# DigiMult_01.net
KiCad netlist of a schematic drawn in EAGLE
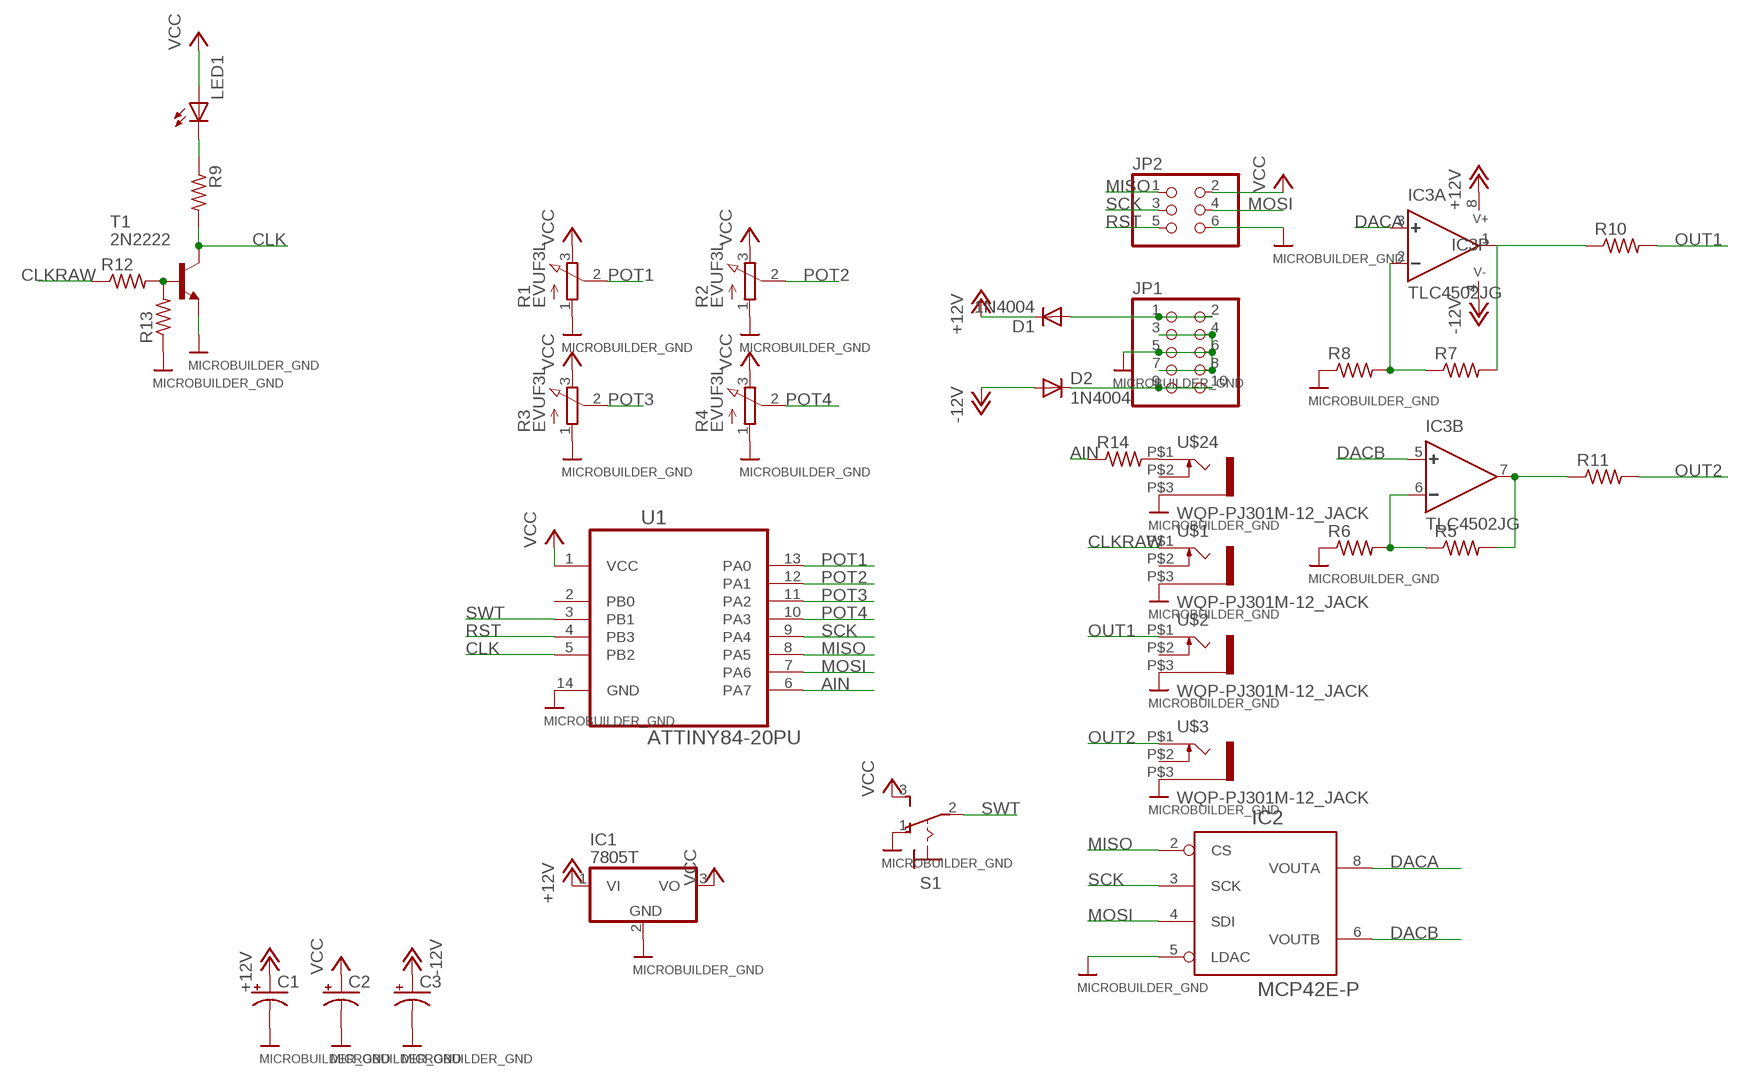
[diagram p0: schematic, sheet 1]

(export (version "E")
  (design (tool "Eeschema 10.0.6"))
  (components
    (comp (ref "C1")
      (value "CPOL-USE2.5-5")
      (footprint "eagle-import:E2,5-5")
      (libsource (lib "eagle-import") (part "CPOL-USE2.5-5"))
    )
    (comp (ref "C2")
      (value "CPOL-USE2.5-5")
      (footprint "eagle-import:E2,5-5")
      (libsource (lib "eagle-import") (part "CPOL-USE2.5-5"))
    )
    (comp (ref "C3")
      (value "CPOL-USE2.5-5")
      (footprint "eagle-import:E2,5-5")
      (libsource (lib "eagle-import") (part "CPOL-USE2.5-5"))
    )
    (comp (ref "D1")
      (value "1N4004")
      (footprint "eagle-import:DO41-10")
      (libsource (lib "eagle-import") (part "1N4004"))
    )
    (comp (ref "D2")
      (value "1N4004")
      (footprint "eagle-import:DO41-10")
      (libsource (lib "eagle-import") (part "1N4004"))
    )
    (comp (ref "IC1")
      (value "7805T")
      (footprint "eagle-import:TO220H")
      (libsource (lib "eagle-import") (part "78T05"))
    )
    (comp (ref "IC2")
      (value "MCP42E-P")
      (footprint "eagle-import:DIL08")
      (libsource (lib "eagle-import") (part "MCP42E-P"))
    )
    (comp (ref "IC3")
      (value "TLC4502JG")
      (footprint "eagle-import:DIL08")
      (libsource (lib "eagle-import") (part "TLC4502JG"))
    )
    (comp (ref "JP1")
      (value "PINHD-2X5/OCT")
      (footprint "eagle-import:2X05")
      (libsource (lib "eagle-import") (part "PINHD-2X5/OCT"))
    )
    (comp (ref "JP2")
      (value "PINHD-2X3/OCT")
      (footprint "eagle-import:2X03")
      (libsource (lib "eagle-import") (part "PINHD-2X3/OCT"))
    )
    (comp (ref "LED1")
      (value "LED3MM")
      (footprint "eagle-import:LED3MM")
      (libsource (lib "eagle-import") (part "LED3MM"))
    )
    (comp (ref "R1")
      (value "EVUF3L")
      (footprint "eagle-import:EVUFXL")
      (libsource (lib "eagle-import") (part "EVULF3"))
    )
    (comp (ref "R2")
      (value "EVUF3L")
      (footprint "eagle-import:EVUFXL")
      (libsource (lib "eagle-import") (part "EVULF3"))
    )
    (comp (ref "R3")
      (value "EVUF3L")
      (footprint "eagle-import:EVUFXL")
      (libsource (lib "eagle-import") (part "EVULF3"))
    )
    (comp (ref "R4")
      (value "EVUF3L")
      (footprint "eagle-import:EVUFXL")
      (libsource (lib "eagle-import") (part "EVULF3"))
    )
    (comp (ref "R5")
      (value "R-US_0204/2V")
      (footprint "eagle-import:0204V")
      (libsource (lib "eagle-import") (part "R-US_0204/2V"))
    )
    (comp (ref "R6")
      (value "R-US_0204/2V")
      (footprint "eagle-import:0204V")
      (libsource (lib "eagle-import") (part "R-US_0204/2V"))
    )
    (comp (ref "R7")
      (value "R-US_0204/2V")
      (footprint "eagle-import:0204V")
      (libsource (lib "eagle-import") (part "R-US_0204/2V"))
    )
    (comp (ref "R8")
      (value "R-US_0204/2V")
      (footprint "eagle-import:0204V")
      (libsource (lib "eagle-import") (part "R-US_0204/2V"))
    )
    (comp (ref "R9")
      (value "R-US_0204/2V")
      (footprint "eagle-import:0204V")
      (libsource (lib "eagle-import") (part "R-US_0204/2V"))
    )
    (comp (ref "R10")
      (value "R-US_0204/2V")
      (footprint "eagle-import:0204V")
      (libsource (lib "eagle-import") (part "R-US_0204/2V"))
    )
    (comp (ref "R11")
      (value "R-US_0204/2V")
      (footprint "eagle-import:0204V")
      (libsource (lib "eagle-import") (part "R-US_0204/2V"))
    )
    (comp (ref "R12")
      (value "R-US_0204/2V")
      (footprint "eagle-import:0204V")
      (libsource (lib "eagle-import") (part "R-US_0204/2V"))
    )
    (comp (ref "R13")
      (value "R-US_0204/2V")
      (footprint "eagle-import:0204V")
      (libsource (lib "eagle-import") (part "R-US_0204/2V"))
    )
    (comp (ref "R14")
      (value "R-US_0204/2V")
      (footprint "eagle-import:0204V")
      (libsource (lib "eagle-import") (part "R-US_0204/2V"))
    )
    (comp (ref "S1")
      (value "M9040P")
      (footprint "eagle-import:M9040P")
      (libsource (lib "eagle-import") (part "M9040P"))
    )
    (comp (ref "T1")
      (value "2N2222")
      (footprint "eagle-import:TO92-EBC-OVAL")
      (libsource (lib "eagle-import") (part "2N2222"))
    )
    (comp (ref "U$1")
      (value "WQP-PJ301M-12_JACK")
      (footprint "eagle-import:WQP-PJ301M-12_JACK")
      (libsource (lib "eagle-import") (part "WQP-PJ301M-12_JACK"))
    )
    (comp (ref "U$2")
      (value "WQP-PJ301M-12_JACK")
      (footprint "eagle-import:WQP-PJ301M-12_JACK")
      (libsource (lib "eagle-import") (part "WQP-PJ301M-12_JACK"))
    )
    (comp (ref "U$3")
      (value "WQP-PJ301M-12_JACK")
      (footprint "eagle-import:WQP-PJ301M-12_JACK")
      (libsource (lib "eagle-import") (part "WQP-PJ301M-12_JACK"))
    )
    (comp (ref "U$24")
      (value "WQP-PJ301M-12_JACK")
      (footprint "eagle-import:WQP-PJ301M-12_JACK")
      (libsource (lib "eagle-import") (part "WQP-PJ301M-12_JACK"))
    )
    (comp (ref "U1")
      (value "ATTINY84-20PU")
      (footprint "eagle-import:DIP254P762X533-14")
      (libsource (lib "eagle-import") (part "ATTINY84-20PU"))
    )
  )
  (nets
    (net (code "1") (name "+12V") (class "Default")
      (node (ref "C1") (pin "+") (pinfunction "+_+") (pintype "passive"))
      (node (ref "D1") (pin "C") (pinfunction "C_C") (pintype "passive"))
      (node (ref "IC1") (pin "1") (pinfunction "VI_1") (pintype "input"))
      (node (ref "IC3") (pin "8") (pinfunction "V+_8") (pintype "power_in"))
    )
    (net (code "2") (name "-12V") (class "Default")
      (node (ref "C3") (pin "+") (pinfunction "+_+") (pintype "passive"))
      (node (ref "D2") (pin "A") (pinfunction "A_A") (pintype "passive"))
      (node (ref "IC3") (pin "4") (pinfunction "V-_4") (pintype "power_in"))
    )
    (net (code "3") (name "/AIN") (class "Default")
      (node (ref "R14") (pin "1") (pinfunction "1_1") (pintype "passive"))
      (node (ref "U1") (pin "6") (pinfunction "PA7_6") (pintype "bidirectional"))
    )
    (net (code "4") (name "/CLK") (class "Default")
      (node (ref "R9") (pin "2") (pinfunction "2_2") (pintype "passive"))
      (node (ref "T1") (pin "C") (pinfunction "C_C") (pintype "passive"))
      (node (ref "U1") (pin "5") (pinfunction "PB2_5") (pintype "bidirectional"))
    )
    (net (code "5") (name "/CLKRAW") (class "Default")
      (node (ref "R12") (pin "1") (pinfunction "1_1") (pintype "passive"))
      (node (ref "U$1") (pin "P$1") (pinfunction "2_P$1") (pintype "passive"))
    )
    (net (code "6") (name "/DACA") (class "Default")
      (node (ref "IC2") (pin "8") (pinfunction "VOUTA_8") (pintype "output"))
      (node (ref "IC3") (pin "3") (pinfunction "+_3") (pintype "input"))
    )
    (net (code "7") (name "/DACB") (class "Default")
      (node (ref "IC2") (pin "6") (pinfunction "VOUTB_6") (pintype "output"))
      (node (ref "IC3") (pin "5") (pinfunction "+_5") (pintype "input"))
    )
    (net (code "8") (name "/MISO") (class "Default")
      (node (ref "IC2") (pin "2") (pinfunction "CS_2") (pintype "input"))
      (node (ref "JP2") (pin "1") (pinfunction "1_1") (pintype "passive"))
      (node (ref "U1") (pin "8") (pinfunction "PA5_8") (pintype "bidirectional"))
    )
    (net (code "9") (name "/MOSI") (class "Default")
      (node (ref "IC2") (pin "4") (pinfunction "SDI_4") (pintype "input"))
      (node (ref "JP2") (pin "4") (pinfunction "4_4") (pintype "passive"))
      (node (ref "U1") (pin "7") (pinfunction "PA6_7") (pintype "bidirectional"))
    )
    (net (code "10") (name "/OUT1") (class "Default")
      (node (ref "R10") (pin "2") (pinfunction "2_2") (pintype "passive"))
      (node (ref "U$2") (pin "P$1") (pinfunction "2_P$1") (pintype "passive"))
    )
    (net (code "11") (name "/OUT2") (class "Default")
      (node (ref "R11") (pin "2") (pinfunction "2_2") (pintype "passive"))
      (node (ref "U$3") (pin "P$1") (pinfunction "2_P$1") (pintype "passive"))
    )
    (net (code "12") (name "/POT1") (class "Default")
      (node (ref "R1") (pin "2") (pinfunction "S_2") (pintype "passive"))
      (node (ref "U1") (pin "13") (pinfunction "PA0_13") (pintype "bidirectional"))
    )
    (net (code "13") (name "/POT2") (class "Default")
      (node (ref "R2") (pin "2") (pinfunction "S_2") (pintype "passive"))
      (node (ref "U1") (pin "12") (pinfunction "PA1_12") (pintype "bidirectional"))
    )
    (net (code "14") (name "/POT3") (class "Default")
      (node (ref "R3") (pin "2") (pinfunction "S_2") (pintype "passive"))
      (node (ref "U1") (pin "11") (pinfunction "PA2_11") (pintype "bidirectional"))
    )
    (net (code "15") (name "/POT4") (class "Default")
      (node (ref "R4") (pin "2") (pinfunction "S_2") (pintype "passive"))
      (node (ref "U1") (pin "10") (pinfunction "PA3_10") (pintype "bidirectional"))
    )
    (net (code "16") (name "/RST") (class "Default")
      (node (ref "JP2") (pin "5") (pinfunction "5_5") (pintype "passive"))
      (node (ref "U1") (pin "4") (pinfunction "PB3_4") (pintype "bidirectional"))
    )
    (net (code "17") (name "/SCK") (class "Default")
      (node (ref "IC2") (pin "3") (pinfunction "SCK_3") (pintype "input"))
      (node (ref "JP2") (pin "3") (pinfunction "3_3") (pintype "passive"))
      (node (ref "U1") (pin "9") (pinfunction "PA4_9") (pintype "bidirectional"))
    )
    (net (code "18") (name "/SWT") (class "Default")
      (node (ref "S1") (pin "2") (pinfunction "P_2") (pintype "passive"))
      (node (ref "U1") (pin "3") (pinfunction "PB1_3") (pintype "bidirectional"))
    )
    (net (code "19") (name "MICROBUILDER_GND") (class "Default")
      (node (ref "C1") (pin "-") (pinfunction "-_-") (pintype "passive"))
      (node (ref "C2") (pin "-") (pinfunction "-_-") (pintype "passive"))
      (node (ref "C3") (pin "-") (pinfunction "-_-") (pintype "passive"))
      (node (ref "IC1") (pin "2") (pinfunction "GND_2") (pintype "passive"))
      (node (ref "IC2") (pin "5") (pinfunction "LDAC_5") (pintype "input"))
      (node (ref "JP1") (pin "3") (pinfunction "3_3") (pintype "passive"))
      (node (ref "JP1") (pin "4") (pinfunction "4_4") (pintype "passive"))
      (node (ref "JP1") (pin "5") (pinfunction "5_5") (pintype "passive"))
      (node (ref "JP1") (pin "6") (pinfunction "6_6") (pintype "passive"))
      (node (ref "JP1") (pin "7") (pinfunction "7_7") (pintype "passive"))
      (node (ref "JP1") (pin "8") (pinfunction "8_8") (pintype "passive"))
      (node (ref "JP2") (pin "6") (pinfunction "6_6") (pintype "passive"))
      (node (ref "R1") (pin "1") (pinfunction "A_1") (pintype "passive"))
      (node (ref "R13") (pin "1") (pinfunction "1_1") (pintype "passive"))
      (node (ref "R2") (pin "1") (pinfunction "A_1") (pintype "passive"))
      (node (ref "R3") (pin "1") (pinfunction "A_1") (pintype "passive"))
      (node (ref "R4") (pin "1") (pinfunction "A_1") (pintype "passive"))
      (node (ref "R6") (pin "1") (pinfunction "1_1") (pintype "passive"))
      (node (ref "R8") (pin "1") (pinfunction "1_1") (pintype "passive"))
      (node (ref "S1") (pin "1") (pinfunction "O_1") (pintype "passive"))
      (node (ref "T1") (pin "E") (pinfunction "E_E") (pintype "passive"))
      (node (ref "U$1") (pin "P$3") (pinfunction "1_P$3") (pintype "passive"))
      (node (ref "U$2") (pin "P$3") (pinfunction "1_P$3") (pintype "passive"))
      (node (ref "U$24") (pin "P$3") (pinfunction "1_P$3") (pintype "passive"))
      (node (ref "U$3") (pin "P$3") (pinfunction "1_P$3") (pintype "passive"))
      (node (ref "U1") (pin "14") (pinfunction "GND_14") (pintype "passive"))
    )
    (net (code "20") (name "Net-(D1-PadA)") (class "Default")
      (node (ref "D1") (pin "A") (pinfunction "A_A") (pintype "passive"))
      (node (ref "JP1") (pin "1") (pinfunction "1_1") (pintype "passive"))
      (node (ref "JP1") (pin "2") (pinfunction "2_2") (pintype "passive"))
    )
    (net (code "21") (name "Net-(D2-PadC)") (class "Default")
      (node (ref "D2") (pin "C") (pinfunction "C_C") (pintype "passive"))
      (node (ref "JP1") (pin "10") (pinfunction "10_10") (pintype "passive"))
      (node (ref "JP1") (pin "9") (pinfunction "9_9") (pintype "passive"))
    )
    (net (code "22") (name "Net-(IC3A--)") (class "Default")
      (node (ref "IC3") (pin "2") (pinfunction "-_2") (pintype "input"))
      (node (ref "R7") (pin "1") (pinfunction "1_1") (pintype "passive"))
      (node (ref "R8") (pin "2") (pinfunction "2_2") (pintype "passive"))
    )
    (net (code "23") (name "Net-(IC3A-OUT)") (class "Default")
      (node (ref "IC3") (pin "1") (pinfunction "OUT_1") (pintype "output"))
      (node (ref "R10") (pin "1") (pinfunction "1_1") (pintype "passive"))
      (node (ref "R7") (pin "2") (pinfunction "2_2") (pintype "passive"))
    )
    (net (code "24") (name "Net-(IC3B--)") (class "Default")
      (node (ref "IC3") (pin "6") (pinfunction "-_6") (pintype "input"))
      (node (ref "R5") (pin "1") (pinfunction "1_1") (pintype "passive"))
      (node (ref "R6") (pin "2") (pinfunction "2_2") (pintype "passive"))
    )
    (net (code "25") (name "Net-(IC3B-OUT)") (class "Default")
      (node (ref "IC3") (pin "7") (pinfunction "OUT_7") (pintype "output"))
      (node (ref "R11") (pin "1") (pinfunction "1_1") (pintype "passive"))
      (node (ref "R5") (pin "2") (pinfunction "2_2") (pintype "passive"))
    )
    (net (code "26") (name "Net-(LED1-C)") (class "Default")
      (node (ref "LED1") (pin "K") (pinfunction "C_K") (pintype "passive"))
      (node (ref "R9") (pin "1") (pinfunction "1_1") (pintype "passive"))
    )
    (net (code "27") (name "Net-(R12-Pad2)") (class "Default")
      (node (ref "R12") (pin "2") (pinfunction "2_2") (pintype "passive"))
      (node (ref "R13") (pin "2") (pinfunction "2_2") (pintype "passive"))
      (node (ref "T1") (pin "B") (pinfunction "B_B") (pintype "passive"))
    )
    (net (code "28") (name "Net-(U$24-2)") (class "Default")
      (node (ref "R14") (pin "2") (pinfunction "2_2") (pintype "passive"))
      (node (ref "U$24") (pin "P$1") (pinfunction "2_P$1") (pintype "passive"))
    )
    (net (code "29") (name "VCC") (class "Default")
      (node (ref "C2") (pin "+") (pinfunction "+_+") (pintype "passive"))
      (node (ref "IC1") (pin "3") (pinfunction "VO_3") (pintype "passive"))
      (node (ref "JP2") (pin "2") (pinfunction "2_2") (pintype "passive"))
      (node (ref "LED1") (pin "A") (pinfunction "A_A") (pintype "passive"))
      (node (ref "R1") (pin "3") (pinfunction "E_3") (pintype "passive"))
      (node (ref "R2") (pin "3") (pinfunction "E_3") (pintype "passive"))
      (node (ref "R3") (pin "3") (pinfunction "E_3") (pintype "passive"))
      (node (ref "R4") (pin "3") (pinfunction "E_3") (pintype "passive"))
      (node (ref "S1") (pin "3") (pinfunction "S_3") (pintype "passive"))
      (node (ref "U1") (pin "1") (pinfunction "VCC_1") (pintype "power_in"))
    )
    (net (code "30") (name "unconnected-(U$1-3-PadP$2)") (class "Default")
      (node (ref "U$1") (pin "P$2") (pinfunction "3_P$2") (pintype "passive"))
    )
    (net (code "31") (name "unconnected-(U$2-3-PadP$2)") (class "Default")
      (node (ref "U$2") (pin "P$2") (pinfunction "3_P$2") (pintype "passive"))
    )
    (net (code "32") (name "unconnected-(U$3-3-PadP$2)") (class "Default")
      (node (ref "U$3") (pin "P$2") (pinfunction "3_P$2") (pintype "passive"))
    )
    (net (code "33") (name "unconnected-(U$24-3-PadP$2)") (class "Default")
      (node (ref "U$24") (pin "P$2") (pinfunction "3_P$2") (pintype "passive"))
    )
    (net (code "34") (name "unconnected-(U1-PB0-Pad2)") (class "Default")
      (node (ref "U1") (pin "2") (pinfunction "PB0_2") (pintype "bidirectional"))
    )
  )
)
